# RomeBoardV1_1.net
KiCad netlist of a schematic drawn in EAGLE
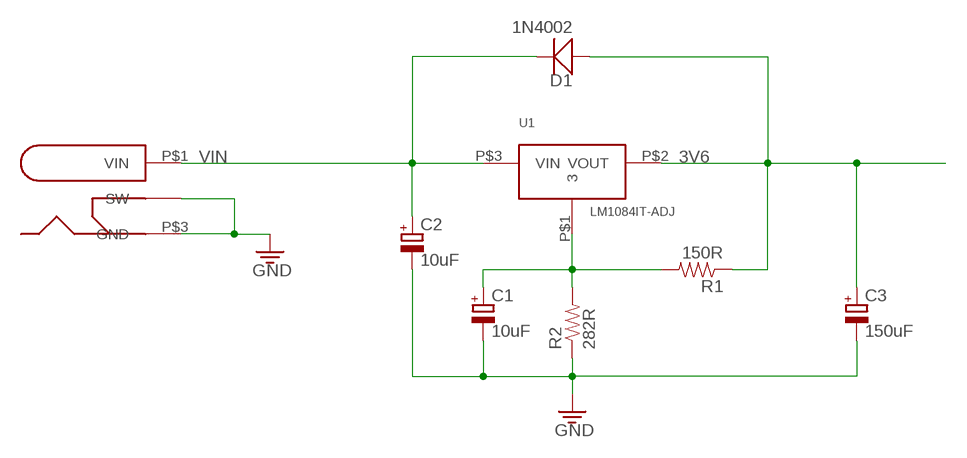
[diagram p0: schematic, sheet 1]
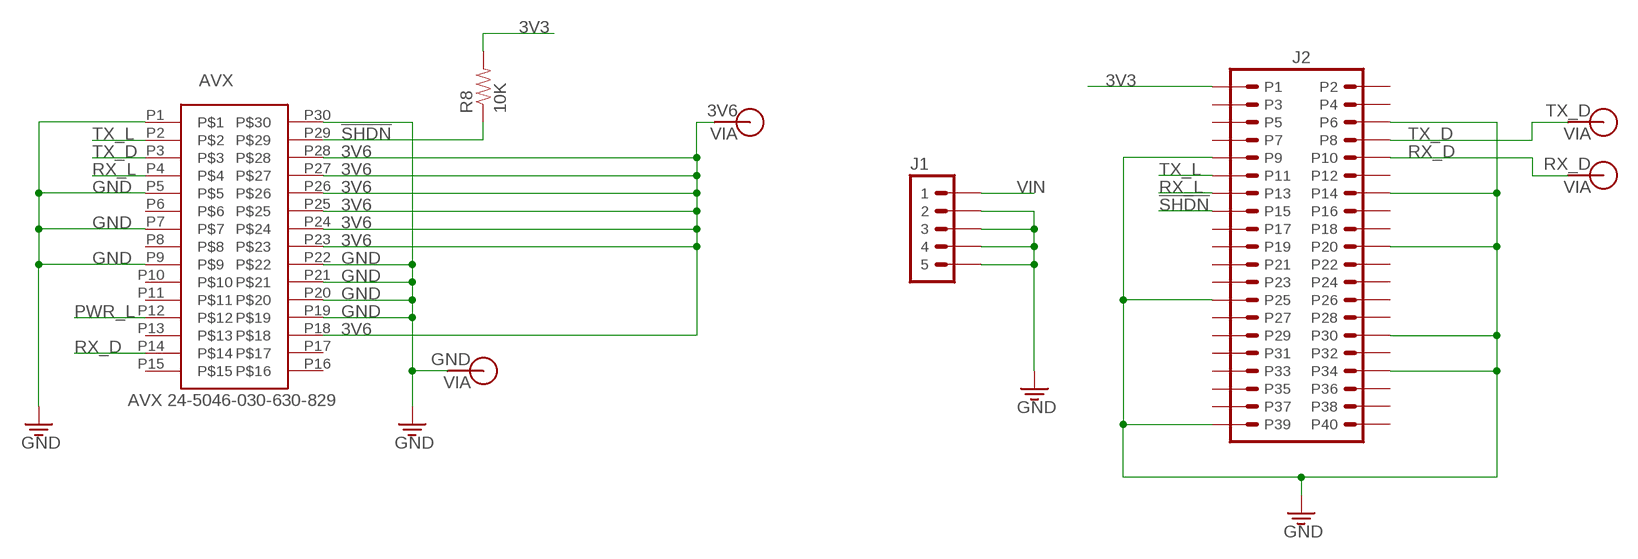
[diagram p1: schematic, sheet 2]
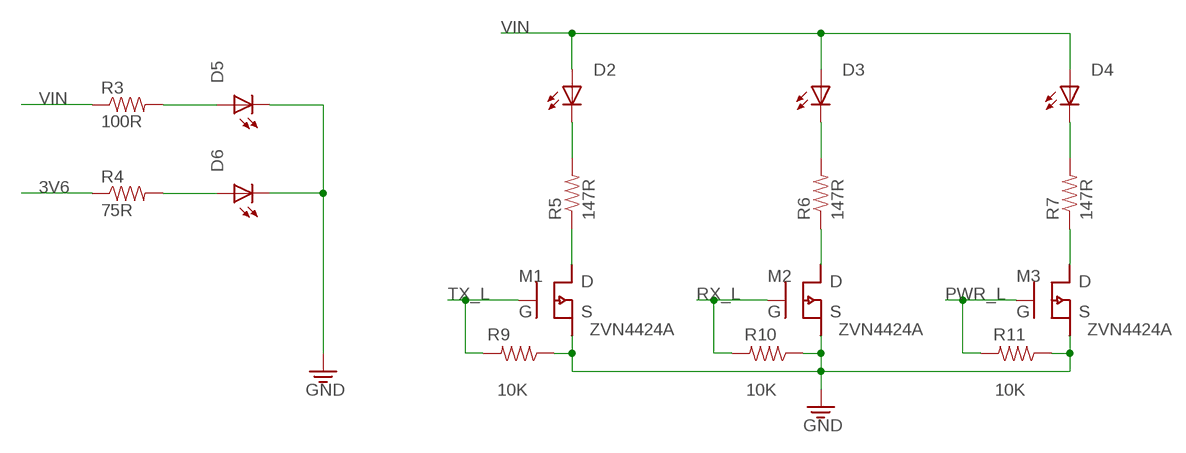
[diagram p2: schematic, sheet 3]
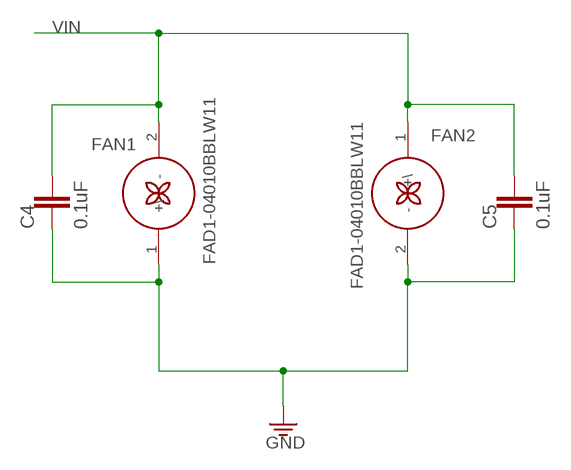
[diagram p3: schematic, sheet 4]

(export (version "E")
  (design (tool "Eeschema 10.0.6"))
  (components
    (comp (ref "AVX")
      (value "AVX-24-5046-030-630-829")
      (footprint "eagle-import:AVX-24-5046-630-829")
      (libsource (lib "eagle-import") (part "AVX-24-5046-030-630-829"))
    )
    (comp (ref "J1")
      (value "HEADER-5")
      (footprint "eagle-import:HEADER-05")
      (libsource (lib "eagle-import") (part "HEADER-5"))
    )
    (comp (ref "J2")
      (value "RASPBERRY-PI-HEADER")
      (footprint "eagle-import:HEADER-20X02")
      (libsource (lib "eagle-import") (part "RASPBERRY-PI-HEADER"))
    )
    (comp (ref "R8")
      (value "10K")
      (footprint "eagle-import:AXIAL-0.4")
      (libsource (lib "eagle-import") (part "RESISTOR-PTH0.4"))
    )
    (comp (ref "V1")
      (value "TX_D")
      (footprint "eagle-import:VIA-120MIL")
      (libsource (lib "eagle-import") (part "VIA-120MIL"))
    )
    (comp (ref "V2")
      (value "RX_D")
      (footprint "eagle-import:VIA-120MIL")
      (libsource (lib "eagle-import") (part "VIA-120MIL"))
    )
    (comp (ref "V4")
      (value "GND")
      (footprint "eagle-import:VIA-120MIL")
      (libsource (lib "eagle-import") (part "VIA-120MIL"))
    )
    (comp (ref "V5")
      (value "3V6")
      (footprint "eagle-import:VIA-120MIL")
      (libsource (lib "eagle-import") (part "VIA-120MIL"))
    )
    (comp (ref "C1")
      (value "10uF")
      (footprint "eagle-import:E2,5-7")
      (libsource (lib "eagle-import") (part "CPOL-EUE2.5-7"))
    )
    (comp (ref "C2")
      (value "10uF")
      (footprint "eagle-import:E2,5-7")
      (libsource (lib "eagle-import") (part "CPOL-EUE2.5-7"))
    )
    (comp (ref "C3")
      (value "150uF")
      (footprint "eagle-import:E5-13")
      (libsource (lib "eagle-import") (part "CPOL-EUE5-13"))
    )
    (comp (ref "D1")
      (value "1N4002")
      (footprint "eagle-import:DO-201AD")
      (libsource (lib "eagle-import") (part "1N4002"))
    )
    (comp (ref "R1")
      (value "150R")
      (footprint "eagle-import:AXIAL-0.4")
      (libsource (lib "eagle-import") (part "RESISTOR-PTH0.4"))
    )
    (comp (ref "R2")
      (value "282R")
      (footprint "eagle-import:AXIAL-0.4")
      (libsource (lib "eagle-import") (part "RESISTOR-PTH0.4"))
    )
    (comp (ref "U$2")
      (value "PJ-002A")
      (footprint "eagle-import:PJ-002A")
      (libsource (lib "eagle-import") (part "PJ-002A"))
    )
    (comp (ref "U1")
      (value "LM1084IT-ADJ")
      (footprint "eagle-import:TO-220-507302B00000G")
      (libsource (lib "eagle-import") (part "LM1084IT-ADJ"))
    )
    (comp (ref "C4")
      (value "0.1uF")
      (footprint "eagle-import:C050-025X075")
      (libsource (lib "eagle-import") (part "CAP5MM-THRU-HOLE"))
    )
    (comp (ref "C5")
      (value "0.1uF")
      (footprint "eagle-import:C050-025X075")
      (libsource (lib "eagle-import") (part "CAP5MM-THRU-HOLE"))
    )
    (comp (ref "FAN1")
      (value "FAD1-04010BBLW11")
      (footprint "eagle-import:1X2-POL")
      (libsource (lib "eagle-import") (part "FAD1-04010BBLW11"))
    )
    (comp (ref "FAN2")
      (value "FAD1-04010BBLW11")
      (footprint "eagle-import:1X2-POL")
      (libsource (lib "eagle-import") (part "FAD1-04010BBLW11"))
    )
    (comp (ref "D2")
      (value "LEDTHRU-HOLE-CONNECTOR")
      (footprint "eagle-import:1X2-POL")
      (libsource (lib "eagle-import") (part "LEDTHRU-HOLE-CONNECTOR"))
    )
    (comp (ref "D3")
      (value "LEDTHRU-HOLE-CONNECTOR")
      (footprint "eagle-import:1X2-POL")
      (libsource (lib "eagle-import") (part "LEDTHRU-HOLE-CONNECTOR"))
    )
    (comp (ref "D4")
      (value "LEDTHRU-HOLE-CONNECTOR")
      (footprint "eagle-import:1X2-POL")
      (libsource (lib "eagle-import") (part "LEDTHRU-HOLE-CONNECTOR"))
    )
    (comp (ref "D5")
      (value "LEDTHRU-HOLE-CONNECTOR")
      (footprint "eagle-import:1X2-POL")
      (libsource (lib "eagle-import") (part "LEDTHRU-HOLE-CONNECTOR"))
    )
    (comp (ref "D6")
      (value "LEDTHRU-HOLE-CONNECTOR")
      (footprint "eagle-import:1X2-POL")
      (libsource (lib "eagle-import") (part "LEDTHRU-HOLE-CONNECTOR"))
    )
    (comp (ref "M1")
      (value "ZVN4424A")
      (footprint "eagle-import:TO-923-MOS")
      (libsource (lib "eagle-import") (part "ZVN4424A"))
    )
    (comp (ref "M2")
      (value "ZVN4424A")
      (footprint "eagle-import:TO-923-MOS")
      (libsource (lib "eagle-import") (part "ZVN4424A"))
    )
    (comp (ref "M3")
      (value "ZVN4424A")
      (footprint "eagle-import:TO-923-MOS")
      (libsource (lib "eagle-import") (part "ZVN4424A"))
    )
    (comp (ref "R3")
      (value "100R")
      (footprint "eagle-import:AXIAL-0.4")
      (libsource (lib "eagle-import") (part "RESISTOR-PTH0.4"))
    )
    (comp (ref "R4")
      (value "75R")
      (footprint "eagle-import:AXIAL-0.4")
      (libsource (lib "eagle-import") (part "RESISTOR-PTH0.4"))
    )
    (comp (ref "R5")
      (value "147R")
      (footprint "eagle-import:AXIAL-0.4")
      (libsource (lib "eagle-import") (part "RESISTOR-PTH0.4"))
    )
    (comp (ref "R6")
      (value "147R")
      (footprint "eagle-import:AXIAL-0.4")
      (libsource (lib "eagle-import") (part "RESISTOR-PTH0.4"))
    )
    (comp (ref "R7")
      (value "147R")
      (footprint "eagle-import:AXIAL-0.4")
      (libsource (lib "eagle-import") (part "RESISTOR-PTH0.4"))
    )
    (comp (ref "R9")
      (value "10K")
      (footprint "eagle-import:AXIAL-0.4")
      (libsource (lib "eagle-import") (part "RESISTOR-PTH0.4"))
    )
    (comp (ref "R10")
      (value "10K")
      (footprint "eagle-import:AXIAL-0.4")
      (libsource (lib "eagle-import") (part "RESISTOR-PTH0.4"))
    )
    (comp (ref "R11")
      (value "10K")
      (footprint "eagle-import:AXIAL-0.4")
      (libsource (lib "eagle-import") (part "RESISTOR-PTH0.4"))
    )
  )
  (nets
    (net (code "1") (name "3V3") (class "Default")
      (node (ref "J2") (pin "P1") (pinfunction "P1_P1") (pintype "passive"))
      (node (ref "R8") (pin "2") (pinfunction "2_2") (pintype "passive"))
    )
    (net (code "2") (name "3V6") (class "Default")
      (node (ref "AVX") (pin "P18") (pinfunction "P$18_P18") (pintype "bidirectional"))
      (node (ref "AVX") (pin "P23") (pinfunction "P$23_P23") (pintype "bidirectional"))
      (node (ref "AVX") (pin "P24") (pinfunction "P$24_P24") (pintype "bidirectional"))
      (node (ref "AVX") (pin "P25") (pinfunction "P$25_P25") (pintype "bidirectional"))
      (node (ref "AVX") (pin "P26") (pinfunction "P$26_P26") (pintype "bidirectional"))
      (node (ref "AVX") (pin "P27") (pinfunction "P$27_P27") (pintype "bidirectional"))
      (node (ref "AVX") (pin "P28") (pinfunction "P$28_P28") (pintype "bidirectional"))
      (node (ref "C3") (pin "+") (pinfunction "+_+") (pintype "passive"))
      (node (ref "D1") (pin "P$1") (pinfunction "A_P$1") (pintype "bidirectional"))
      (node (ref "R1") (pin "1") (pinfunction "1_1") (pintype "passive"))
      (node (ref "R4") (pin "1") (pinfunction "1_1") (pintype "passive"))
      (node (ref "U1") (pin "P$2") (pinfunction "VOUT_P$2") (pintype "bidirectional"))
      (node (ref "V5") (pin "P$1") (pinfunction "P$1_P$1") (pintype "bidirectional"))
    )
    (net (code "3") (name "GND") (class "Default")
      (node (ref "AVX") (pin "P1") (pinfunction "P$1_P1") (pintype "bidirectional"))
      (node (ref "AVX") (pin "P19") (pinfunction "P$19_P19") (pintype "bidirectional"))
      (node (ref "AVX") (pin "P20") (pinfunction "P$20_P20") (pintype "bidirectional"))
      (node (ref "AVX") (pin "P21") (pinfunction "P$21_P21") (pintype "bidirectional"))
      (node (ref "AVX") (pin "P22") (pinfunction "P$22_P22") (pintype "bidirectional"))
      (node (ref "AVX") (pin "P30") (pinfunction "P$30_P30") (pintype "bidirectional"))
      (node (ref "AVX") (pin "P5") (pinfunction "P$5_P5") (pintype "bidirectional"))
      (node (ref "AVX") (pin "P7") (pinfunction "P$7_P7") (pintype "bidirectional"))
      (node (ref "AVX") (pin "P9") (pinfunction "P$9_P9") (pintype "bidirectional"))
      (node (ref "C1") (pin "-") (pinfunction "-_-") (pintype "passive"))
      (node (ref "C2") (pin "-") (pinfunction "-_-") (pintype "passive"))
      (node (ref "C3") (pin "-") (pinfunction "-_-") (pintype "passive"))
      (node (ref "C4") (pin "2") (pinfunction "P$2_2") (pintype "passive"))
      (node (ref "C5") (pin "2") (pinfunction "P$2_2") (pintype "passive"))
      (node (ref "D5") (pin "2") (pinfunction "C_2") (pintype "passive"))
      (node (ref "D6") (pin "2") (pinfunction "C_2") (pintype "passive"))
      (node (ref "FAN1") (pin "1") (pinfunction "+\\_1") (pintype "bidirectional"))
      (node (ref "FAN2") (pin "2") (pinfunction "-_2") (pintype "bidirectional"))
      (node (ref "J1") (pin "2") (pinfunction "2_2") (pintype "passive"))
      (node (ref "J1") (pin "3") (pinfunction "3_3") (pintype "passive"))
      (node (ref "J1") (pin "4") (pinfunction "4_4") (pintype "passive"))
      (node (ref "J1") (pin "5") (pinfunction "5_5") (pintype "passive"))
      (node (ref "J2") (pin "P14") (pinfunction "P14_P14") (pintype "passive"))
      (node (ref "J2") (pin "P20") (pinfunction "P20_P20") (pintype "passive"))
      (node (ref "J2") (pin "P25") (pinfunction "P25_P25") (pintype "passive"))
      (node (ref "J2") (pin "P30") (pinfunction "P30_P30") (pintype "passive"))
      (node (ref "J2") (pin "P34") (pinfunction "P34_P34") (pintype "passive"))
      (node (ref "J2") (pin "P39") (pinfunction "P39_P39") (pintype "passive"))
      (node (ref "J2") (pin "P6") (pinfunction "P6_P6") (pintype "passive"))
      (node (ref "J2") (pin "P9") (pinfunction "P9_P9") (pintype "passive"))
      (node (ref "M1") (pin "3") (pinfunction "S_3") (pintype "bidirectional"))
      (node (ref "M2") (pin "3") (pinfunction "S_3") (pintype "bidirectional"))
      (node (ref "M3") (pin "3") (pinfunction "S_3") (pintype "bidirectional"))
      (node (ref "R10") (pin "1") (pinfunction "1_1") (pintype "passive"))
      (node (ref "R11") (pin "1") (pinfunction "1_1") (pintype "passive"))
      (node (ref "R2") (pin "1") (pinfunction "1_1") (pintype "passive"))
      (node (ref "R9") (pin "1") (pinfunction "1_1") (pintype "passive"))
      (node (ref "U$2") (pin "P$2") (pinfunction "SW_P$2") (pintype "bidirectional"))
      (node (ref "U$2") (pin "P$3") (pinfunction "GND_P$3") (pintype "bidirectional"))
      (node (ref "V4") (pin "P$1") (pinfunction "P$1_P$1") (pintype "bidirectional"))
    )
    (net (code "4") (name "Net-(D2-C)") (class "Default")
      (node (ref "D2") (pin "2") (pinfunction "C_2") (pintype "passive"))
      (node (ref "R5") (pin "2") (pinfunction "2_2") (pintype "passive"))
    )
    (net (code "5") (name "Net-(D3-C)") (class "Default")
      (node (ref "D3") (pin "2") (pinfunction "C_2") (pintype "passive"))
      (node (ref "R6") (pin "2") (pinfunction "2_2") (pintype "passive"))
    )
    (net (code "6") (name "Net-(D4-C)") (class "Default")
      (node (ref "D4") (pin "2") (pinfunction "C_2") (pintype "passive"))
      (node (ref "R7") (pin "2") (pinfunction "2_2") (pintype "passive"))
    )
    (net (code "7") (name "Net-(D5-A)") (class "Default")
      (node (ref "D5") (pin "1") (pinfunction "A_1") (pintype "passive"))
      (node (ref "R3") (pin "2") (pinfunction "2_2") (pintype "passive"))
    )
    (net (code "8") (name "Net-(D6-A)") (class "Default")
      (node (ref "D6") (pin "1") (pinfunction "A_1") (pintype "passive"))
      (node (ref "R4") (pin "2") (pinfunction "2_2") (pintype "passive"))
    )
    (net (code "9") (name "Net-(M1-D)") (class "Default")
      (node (ref "M1") (pin "1") (pinfunction "D_1") (pintype "bidirectional"))
      (node (ref "R5") (pin "1") (pinfunction "1_1") (pintype "passive"))
    )
    (net (code "10") (name "Net-(M2-D)") (class "Default")
      (node (ref "M2") (pin "1") (pinfunction "D_1") (pintype "bidirectional"))
      (node (ref "R6") (pin "1") (pinfunction "1_1") (pintype "passive"))
    )
    (net (code "11") (name "Net-(M3-D)") (class "Default")
      (node (ref "M3") (pin "1") (pinfunction "D_1") (pintype "bidirectional"))
      (node (ref "R7") (pin "1") (pinfunction "1_1") (pintype "passive"))
    )
    (net (code "12") (name "Net-(U1-3)") (class "Default")
      (node (ref "C1") (pin "+") (pinfunction "+_+") (pintype "passive"))
      (node (ref "R1") (pin "2") (pinfunction "2_2") (pintype "passive"))
      (node (ref "R2") (pin "2") (pinfunction "2_2") (pintype "passive"))
      (node (ref "U1") (pin "P$1") (pinfunction "3_P$1") (pintype "bidirectional"))
    )
    (net (code "13") (name "PWR_L") (class "Default")
      (node (ref "AVX") (pin "P12") (pinfunction "P$12_P12") (pintype "bidirectional"))
      (node (ref "M3") (pin "2") (pinfunction "G_2") (pintype "bidirectional"))
      (node (ref "R11") (pin "2") (pinfunction "2_2") (pintype "passive"))
    )
    (net (code "14") (name "RX_D") (class "Default")
      (node (ref "AVX") (pin "P14") (pinfunction "P$14_P14") (pintype "bidirectional"))
      (node (ref "J2") (pin "P10") (pinfunction "P10_P10") (pintype "passive"))
      (node (ref "V2") (pin "P$1") (pinfunction "P$1_P$1") (pintype "bidirectional"))
    )
    (net (code "15") (name "RX_L") (class "Default")
      (node (ref "AVX") (pin "P4") (pinfunction "P$4_P4") (pintype "bidirectional"))
      (node (ref "J2") (pin "P13") (pinfunction "P13_P13") (pintype "passive"))
      (node (ref "M2") (pin "2") (pinfunction "G_2") (pintype "bidirectional"))
      (node (ref "R10") (pin "2") (pinfunction "2_2") (pintype "passive"))
    )
    (net (code "16") (name "TX_D") (class "Default")
      (node (ref "AVX") (pin "P3") (pinfunction "P$3_P3") (pintype "bidirectional"))
      (node (ref "J2") (pin "P8") (pinfunction "P8_P8") (pintype "passive"))
      (node (ref "V1") (pin "P$1") (pinfunction "P$1_P$1") (pintype "bidirectional"))
    )
    (net (code "17") (name "TX_L") (class "Default")
      (node (ref "AVX") (pin "P2") (pinfunction "P$2_P2") (pintype "bidirectional"))
      (node (ref "J2") (pin "P11") (pinfunction "P11_P11") (pintype "passive"))
      (node (ref "M1") (pin "2") (pinfunction "G_2") (pintype "bidirectional"))
      (node (ref "R9") (pin "2") (pinfunction "2_2") (pintype "passive"))
    )
    (net (code "18") (name "VIN") (class "Default")
      (node (ref "C2") (pin "+") (pinfunction "+_+") (pintype "passive"))
      (node (ref "C4") (pin "1") (pinfunction "P$1_1") (pintype "passive"))
      (node (ref "C5") (pin "1") (pinfunction "P$1_1") (pintype "passive"))
      (node (ref "D1") (pin "P$2") (pinfunction "C_P$2") (pintype "bidirectional"))
      (node (ref "D2") (pin "1") (pinfunction "A_1") (pintype "passive"))
      (node (ref "D3") (pin "1") (pinfunction "A_1") (pintype "passive"))
      (node (ref "D4") (pin "1") (pinfunction "A_1") (pintype "passive"))
      (node (ref "FAN1") (pin "2") (pinfunction "-_2") (pintype "bidirectional"))
      (node (ref "FAN2") (pin "1") (pinfunction "+\\_1") (pintype "bidirectional"))
      (node (ref "J1") (pin "1") (pinfunction "1_1") (pintype "passive"))
      (node (ref "R3") (pin "1") (pinfunction "1_1") (pintype "passive"))
      (node (ref "U$2") (pin "P$1") (pinfunction "VIN_P$1") (pintype "bidirectional"))
      (node (ref "U1") (pin "P$3") (pinfunction "VIN_P$3") (pintype "bidirectional"))
    )
    (net (code "19") (name "unconnected-(AVX-P$6-PadP6)") (class "Default")
      (node (ref "AVX") (pin "P6") (pinfunction "P$6_P6") (pintype "bidirectional"))
    )
    (net (code "20") (name "unconnected-(AVX-P$8-PadP8)") (class "Default")
      (node (ref "AVX") (pin "P8") (pinfunction "P$8_P8") (pintype "bidirectional"))
    )
    (net (code "21") (name "unconnected-(AVX-P$10-PadP10)") (class "Default")
      (node (ref "AVX") (pin "P10") (pinfunction "P$10_P10") (pintype "bidirectional"))
    )
    (net (code "22") (name "unconnected-(AVX-P$11-PadP11)") (class "Default")
      (node (ref "AVX") (pin "P11") (pinfunction "P$11_P11") (pintype "bidirectional"))
    )
    (net (code "23") (name "unconnected-(AVX-P$13-PadP13)") (class "Default")
      (node (ref "AVX") (pin "P13") (pinfunction "P$13_P13") (pintype "bidirectional"))
    )
    (net (code "24") (name "unconnected-(AVX-P$15-PadP15)") (class "Default")
      (node (ref "AVX") (pin "P15") (pinfunction "P$15_P15") (pintype "bidirectional"))
    )
    (net (code "25") (name "unconnected-(AVX-P$16-PadP16)") (class "Default")
      (node (ref "AVX") (pin "P16") (pinfunction "P$16_P16") (pintype "bidirectional"))
    )
    (net (code "26") (name "unconnected-(AVX-P$17-PadP17)") (class "Default")
      (node (ref "AVX") (pin "P17") (pinfunction "P$17_P17") (pintype "bidirectional"))
    )
    (net (code "27") (name "unconnected-(J2-PadP2)") (class "Default")
      (node (ref "J2") (pin "P2") (pinfunction "P2_P2") (pintype "passive"))
    )
    (net (code "28") (name "unconnected-(J2-PadP3)") (class "Default")
      (node (ref "J2") (pin "P3") (pinfunction "P3_P3") (pintype "passive"))
    )
    (net (code "29") (name "unconnected-(J2-PadP4)") (class "Default")
      (node (ref "J2") (pin "P4") (pinfunction "P4_P4") (pintype "passive"))
    )
    (net (code "30") (name "unconnected-(J2-PadP5)") (class "Default")
      (node (ref "J2") (pin "P5") (pinfunction "P5_P5") (pintype "passive"))
    )
    (net (code "31") (name "unconnected-(J2-PadP7)") (class "Default")
      (node (ref "J2") (pin "P7") (pinfunction "P7_P7") (pintype "passive"))
    )
    (net (code "32") (name "unconnected-(J2-PadP12)") (class "Default")
      (node (ref "J2") (pin "P12") (pinfunction "P12_P12") (pintype "passive"))
    )
    (net (code "33") (name "unconnected-(J2-PadP16)") (class "Default")
      (node (ref "J2") (pin "P16") (pinfunction "P16_P16") (pintype "passive"))
    )
    (net (code "34") (name "unconnected-(J2-PadP17)") (class "Default")
      (node (ref "J2") (pin "P17") (pinfunction "P17_P17") (pintype "passive"))
    )
    (net (code "35") (name "unconnected-(J2-PadP18)") (class "Default")
      (node (ref "J2") (pin "P18") (pinfunction "P18_P18") (pintype "passive"))
    )
    (net (code "36") (name "unconnected-(J2-PadP19)") (class "Default")
      (node (ref "J2") (pin "P19") (pinfunction "P19_P19") (pintype "passive"))
    )
    (net (code "37") (name "unconnected-(J2-PadP21)") (class "Default")
      (node (ref "J2") (pin "P21") (pinfunction "P21_P21") (pintype "passive"))
    )
    (net (code "38") (name "unconnected-(J2-PadP22)") (class "Default")
      (node (ref "J2") (pin "P22") (pinfunction "P22_P22") (pintype "passive"))
    )
    (net (code "39") (name "unconnected-(J2-PadP23)") (class "Default")
      (node (ref "J2") (pin "P23") (pinfunction "P23_P23") (pintype "passive"))
    )
    (net (code "40") (name "unconnected-(J2-PadP24)") (class "Default")
      (node (ref "J2") (pin "P24") (pinfunction "P24_P24") (pintype "passive"))
    )
    (net (code "41") (name "unconnected-(J2-PadP26)") (class "Default")
      (node (ref "J2") (pin "P26") (pinfunction "P26_P26") (pintype "passive"))
    )
    (net (code "42") (name "unconnected-(J2-PadP27)") (class "Default")
      (node (ref "J2") (pin "P27") (pinfunction "P27_P27") (pintype "passive"))
    )
    (net (code "43") (name "unconnected-(J2-PadP28)") (class "Default")
      (node (ref "J2") (pin "P28") (pinfunction "P28_P28") (pintype "passive"))
    )
    (net (code "44") (name "unconnected-(J2-PadP29)") (class "Default")
      (node (ref "J2") (pin "P29") (pinfunction "P29_P29") (pintype "passive"))
    )
    (net (code "45") (name "unconnected-(J2-PadP31)") (class "Default")
      (node (ref "J2") (pin "P31") (pinfunction "P31_P31") (pintype "passive"))
    )
    (net (code "46") (name "unconnected-(J2-PadP32)") (class "Default")
      (node (ref "J2") (pin "P32") (pinfunction "P32_P32") (pintype "passive"))
    )
    (net (code "47") (name "unconnected-(J2-PadP33)") (class "Default")
      (node (ref "J2") (pin "P33") (pinfunction "P33_P33") (pintype "passive"))
    )
    (net (code "48") (name "unconnected-(J2-PadP35)") (class "Default")
      (node (ref "J2") (pin "P35") (pinfunction "P35_P35") (pintype "passive"))
    )
    (net (code "49") (name "unconnected-(J2-PadP36)") (class "Default")
      (node (ref "J2") (pin "P36") (pinfunction "P36_P36") (pintype "passive"))
    )
    (net (code "50") (name "unconnected-(J2-PadP37)") (class "Default")
      (node (ref "J2") (pin "P37") (pinfunction "P37_P37") (pintype "passive"))
    )
    (net (code "51") (name "unconnected-(J2-PadP38)") (class "Default")
      (node (ref "J2") (pin "P38") (pinfunction "P38_P38") (pintype "passive"))
    )
    (net (code "52") (name "unconnected-(J2-PadP40)") (class "Default")
      (node (ref "J2") (pin "P40") (pinfunction "P40_P40") (pintype "passive"))
    )
    (net (code "53") (name "~{SHDN}") (class "Default")
      (node (ref "AVX") (pin "P29") (pinfunction "P$29_P29") (pintype "bidirectional"))
      (node (ref "J2") (pin "P15") (pinfunction "P15_P15") (pintype "passive"))
      (node (ref "R8") (pin "1") (pinfunction "1_1") (pintype "passive"))
    )
  )
)
